# Breakout_SoC.net
KiCad netlist of a schematic drawn in Altium Designer
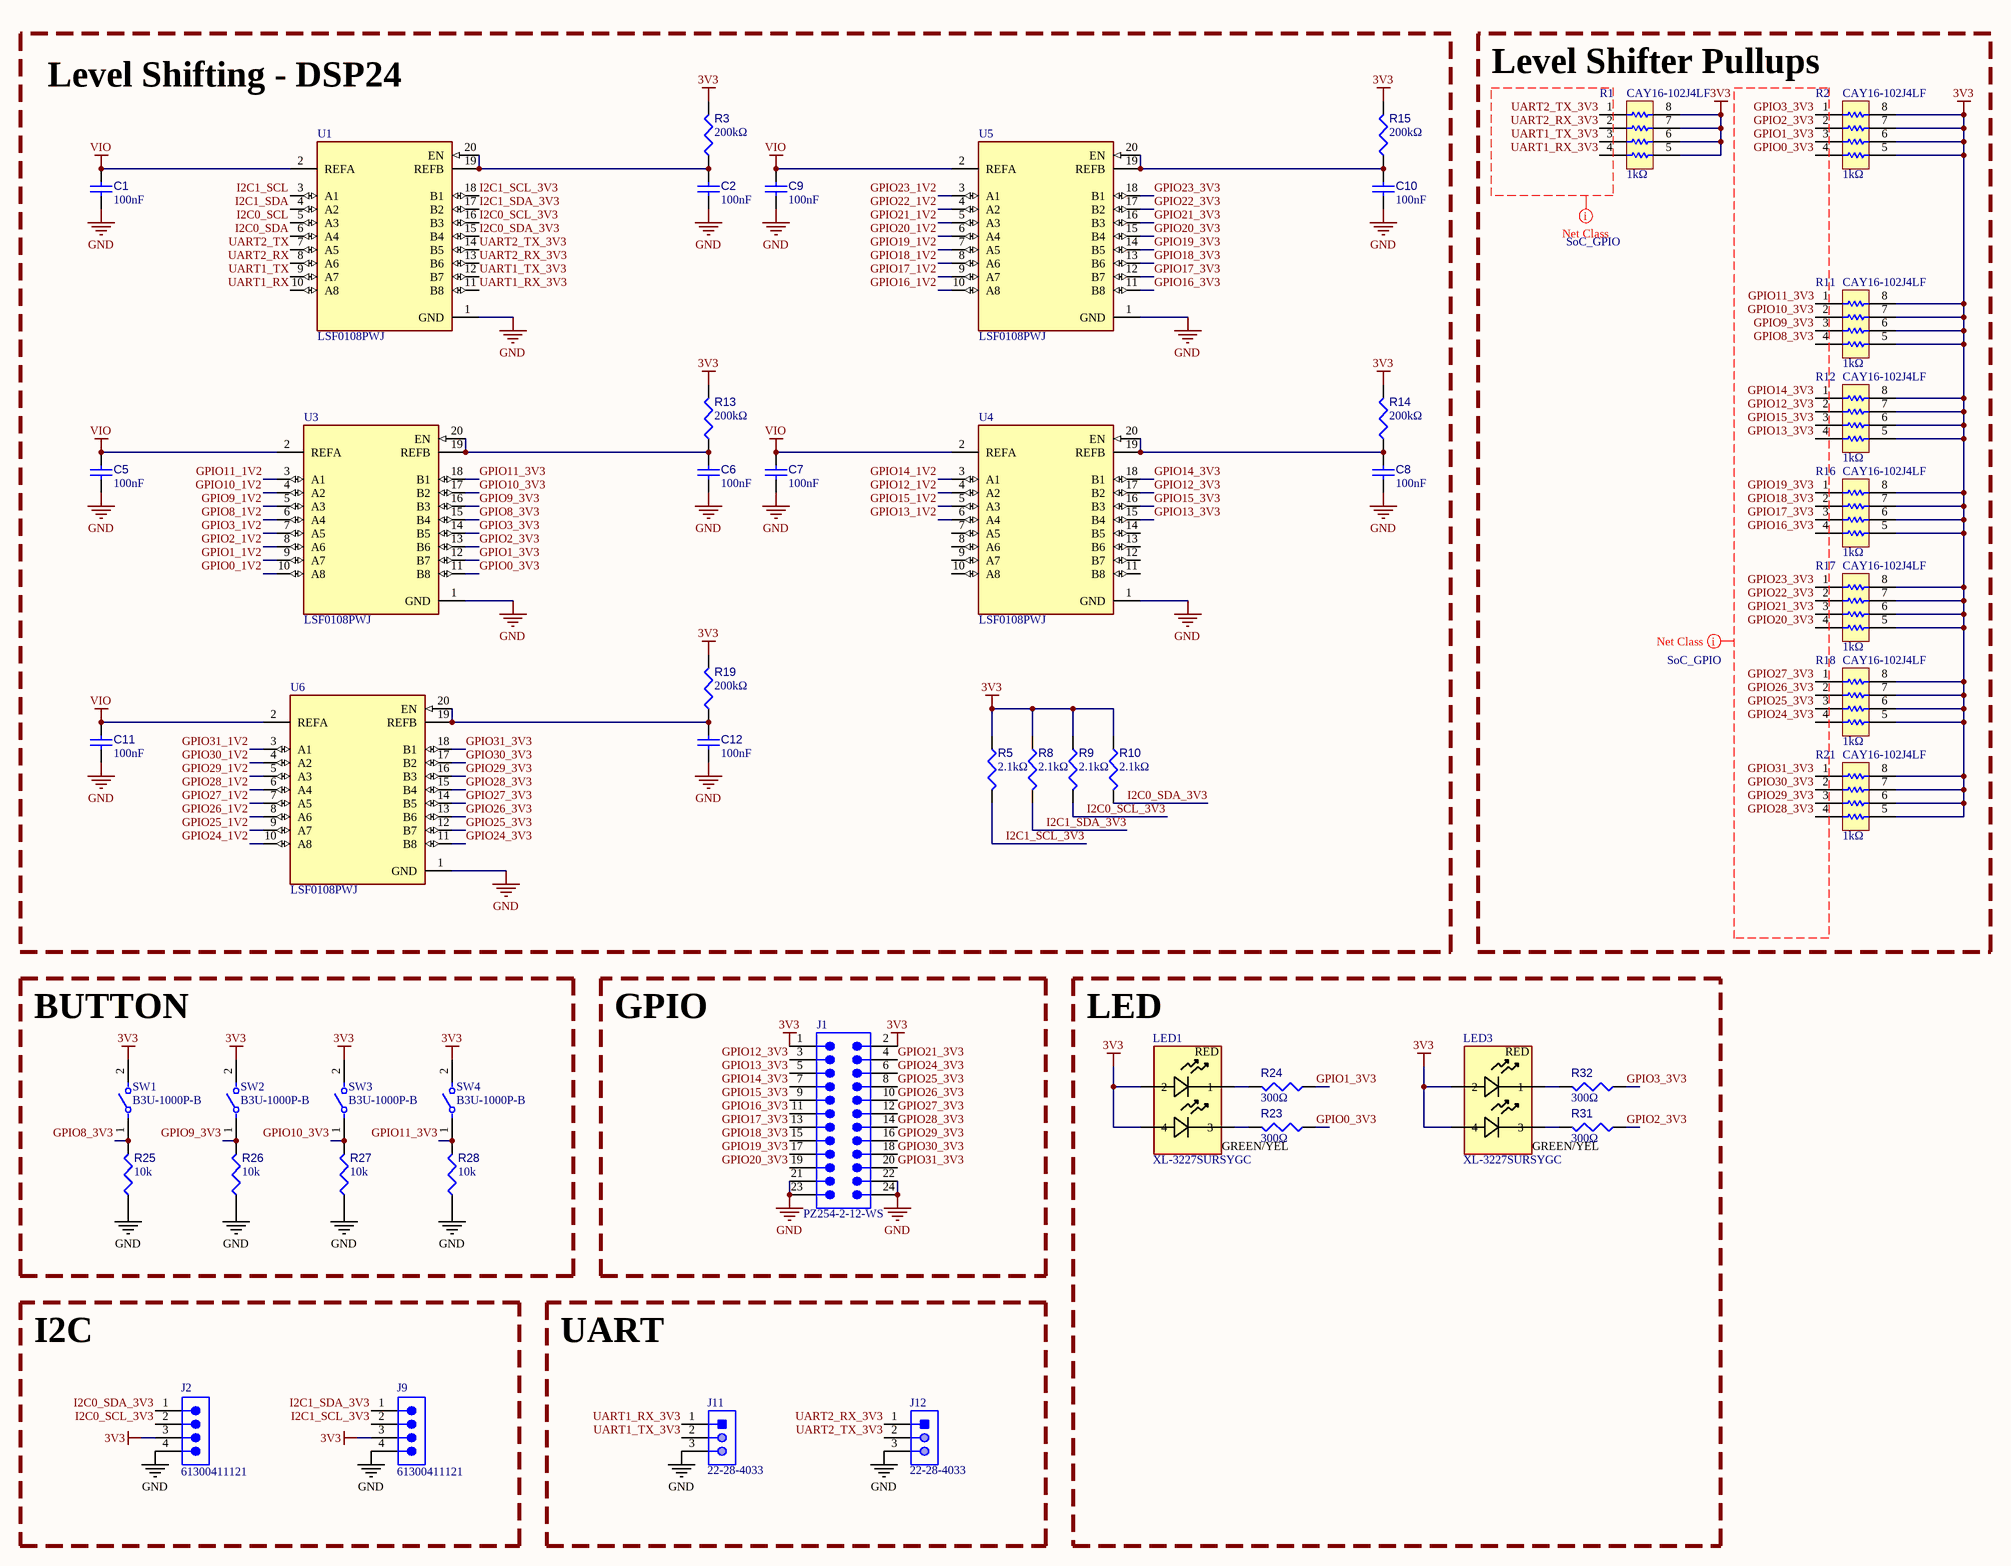
[diagram p0: Breakout_SoC.SchDoc]

(export (version "E")
  (design (tool "Eeschema 10.0.6"))
  (components
    (comp (ref "C1")
      (value "100nF")
      (footprint "CAP-0402-MFG")
      (description "0402-100n-10%-16V-X7R-AECQ200")
      (fields (field (name "TOLERANCE") "10%") (field (name "MANUFACTURER PART NUMBER") "CL05B104KO5VPNC"))
      (libsource (lib "UC Berkeley – EE194") (part "CAP-NP-2P"))
    )
    (comp (ref "C2")
      (value "100nF")
      (footprint "CAP-0402-MFG")
      (description "0402-100n-10%-16V-X7R-AECQ200")
      (fields (field (name "TOLERANCE") "10%") (field (name "MANUFACTURER PART NUMBER") "CL05B104KO5VPNC"))
      (libsource (lib "UC Berkeley – EE194") (part "CAP-NP-2P"))
    )
    (comp (ref "C5")
      (value "100nF")
      (footprint "CAP-0402-MFG")
      (description "0402-100n-10%-16V-X7R-AECQ200")
      (fields (field (name "TOLERANCE") "10%") (field (name "MANUFACTURER PART NUMBER") "CL05B104KO5VPNC"))
      (libsource (lib "UC Berkeley – EE194") (part "CAP-NP-2P"))
    )
    (comp (ref "C6")
      (value "100nF")
      (footprint "CAP-0402-MFG")
      (description "0402-100n-10%-16V-X7R-AECQ200")
      (fields (field (name "TOLERANCE") "10%") (field (name "MANUFACTURER PART NUMBER") "CL05B104KO5VPNC"))
      (libsource (lib "UC Berkeley – EE194") (part "CAP-NP-2P"))
    )
    (comp (ref "C7")
      (value "100nF")
      (footprint "CAP-0402-MFG")
      (description "0402-100n-10%-16V-X7R-AECQ200")
      (fields (field (name "TOLERANCE") "10%") (field (name "MANUFACTURER PART NUMBER") "CL05B104KO5VPNC"))
      (libsource (lib "UC Berkeley – EE194") (part "CAP-NP-2P"))
    )
    (comp (ref "C8")
      (value "100nF")
      (footprint "CAP-0402-MFG")
      (description "0402-100n-10%-16V-X7R-AECQ200")
      (fields (field (name "TOLERANCE") "10%") (field (name "MANUFACTURER PART NUMBER") "CL05B104KO5VPNC"))
      (libsource (lib "UC Berkeley – EE194") (part "CAP-NP-2P"))
    )
    (comp (ref "C9")
      (value "100nF")
      (footprint "CAP-0402-MFG")
      (description "0402-100n-10%-16V-X7R-AECQ200")
      (fields (field (name "TOLERANCE") "10%") (field (name "MANUFACTURER PART NUMBER") "CL05B104KO5VPNC"))
      (libsource (lib "UC Berkeley – EE194") (part "CAP-NP-2P"))
    )
    (comp (ref "C10")
      (value "100nF")
      (footprint "CAP-0402-MFG")
      (description "0402-100n-10%-16V-X7R-AECQ200")
      (fields (field (name "TOLERANCE") "10%") (field (name "MANUFACTURER PART NUMBER") "CL05B104KO5VPNC"))
      (libsource (lib "UC Berkeley – EE194") (part "CAP-NP-2P"))
    )
    (comp (ref "C11")
      (value "100nF")
      (footprint "CAP-0402-MFG")
      (description "0402-100n-10%-16V-X7R-AECQ200")
      (fields (field (name "TOLERANCE") "10%") (field (name "MANUFACTURER PART NUMBER") "CL05B104KO5VPNC"))
      (libsource (lib "UC Berkeley – EE194") (part "CAP-NP-2P"))
    )
    (comp (ref "C12")
      (value "100nF")
      (footprint "CAP-0402-MFG")
      (description "0402-100n-10%-16V-X7R-AECQ200")
      (fields (field (name "TOLERANCE") "10%") (field (name "MANUFACTURER PART NUMBER") "CL05B104KO5VPNC"))
      (libsource (lib "UC Berkeley – EE194") (part "CAP-NP-2P"))
    )
    (comp (ref "J1")
      (value "PZ254-2-12-WS")
      (footprint "610124249121")
      (description "Pin Header, 2.54MM Pitch, SMT Double Row Right Angled, 24 Pins")
      (libsource (lib "UC Berkeley – EE194") (part "Header_Male_2R_24P"))
    )
    (comp (ref "J2")
      (value "61300411121")
      (footprint "61300411121")
      (description "Conn Unshrouded Header HDR 4 POS 2.54mm Solder ST Thru-Hole Bag")
      (libsource (lib "UC Berkeley – EE194") (part "HEADER-MALE-4P-1R"))
    )
    (comp (ref "J9")
      (value "61300411121")
      (footprint "61300411121")
      (description "Conn Unshrouded Header HDR 4 POS 2.54mm Solder ST Thru-Hole Bag")
      (libsource (lib "UC Berkeley – EE194") (part "HEADER-MALE-4P-1R"))
    )
    (comp (ref "J11")
      (value "22-28-4033")
      (footprint "MOLX-22-28-4033_V")
      (libsource (lib "UC Berkeley – EE194") (part "HEADER-MALE-3P-1R"))
    )
    (comp (ref "J12")
      (value "22-28-4033")
      (footprint "MOLX-22-28-4033_V")
      (libsource (lib "UC Berkeley – EE194") (part "HEADER-MALE-3P-1R"))
    )
    (comp (ref "LED1")
      (value "XL-3227SURSYGC")
      (footprint "LED-1210-4P-MFG")
      (description "LED indicator light dual color red yellow green 1210 front facing")
      (libsource (lib "UC Berkeley – EE194") (part "LED-2COLOR-4P"))
    )
    (comp (ref "LED3")
      (value "XL-3227SURSYGC")
      (footprint "LED-1210-4P-MFG")
      (description "LED indicator light dual color red yellow green 1210 front facing")
      (libsource (lib "UC Berkeley – EE194") (part "LED-2COLOR-4P"))
    )
    (comp (ref "R1")
      (value "CAY16-102J4LF")
      (footprint "RES-4x0603-MFG")
      (description "Res Thick Film Array 1K Ohm 5% 0.25W(1/4W) ±200ppm/C ISOL 8-Pin 1206(4 X 0603) Convex SMD T/R")
      (fields (field (name "TOLERANCE") "5%") (field (name "ALTIUM_VALUE") "1kΩ"))
      (libsource (lib "UC Berkeley – EE194") (part "RES-x4-8P"))
    )
    (comp (ref "R2")
      (value "CAY16-102J4LF")
      (footprint "RES-4x0603-MFG")
      (description "Res Thick Film Array 1K Ohm 5% 0.25W(1/4W) ±200ppm/C ISOL 8-Pin 1206(4 X 0603) Convex SMD T/R")
      (fields (field (name "TOLERANCE") "5%") (field (name "ALTIUM_VALUE") "1kΩ"))
      (libsource (lib "UC Berkeley – EE194") (part "RES-x4-8P"))
    )
    (comp (ref "R3")
      (value "200kΩ")
      (footprint "RES-0402")
      (description "0402-200k-1%-1/16W-AEC-Q200")
      (fields (field (name "TOLERANCE") "1%") (field (name "POWER") "63mW"))
      (libsource (lib "UC Berkeley – EE194") (part "RES-2P"))
    )
    (comp (ref "R5")
      (value "2.1kΩ")
      (footprint "RES-0402")
      (description "0402-2.1k-1%-1/16W-AEC-Q200")
      (fields (field (name "POWER") "63mW") (field (name "MANUFACTURER PART NUMBER") "CRCW04022K10FKED"))
      (libsource (lib "UC Berkeley – EE194") (part "RES-2P"))
    )
    (comp (ref "R8")
      (value "2.1kΩ")
      (footprint "RES-0402")
      (description "0402-2.1k-1%-1/16W-AEC-Q200")
      (fields (field (name "POWER") "63mW") (field (name "MANUFACTURER PART NUMBER") "CRCW04022K10FKED"))
      (libsource (lib "UC Berkeley – EE194") (part "RES-2P"))
    )
    (comp (ref "R9")
      (value "2.1kΩ")
      (footprint "RES-0402")
      (description "0402-2.1k-1%-1/16W-AEC-Q200")
      (fields (field (name "POWER") "63mW") (field (name "MANUFACTURER PART NUMBER") "CRCW04022K10FKED"))
      (libsource (lib "UC Berkeley – EE194") (part "RES-2P"))
    )
    (comp (ref "R10")
      (value "2.1kΩ")
      (footprint "RES-0402")
      (description "0402-2.1k-1%-1/16W-AEC-Q200")
      (fields (field (name "POWER") "63mW") (field (name "MANUFACTURER PART NUMBER") "CRCW04022K10FKED"))
      (libsource (lib "UC Berkeley – EE194") (part "RES-2P"))
    )
    (comp (ref "R11")
      (value "CAY16-102J4LF")
      (footprint "RES-4x0603-MFG")
      (description "Res Thick Film Array 1K Ohm 5% 0.25W(1/4W) ±200ppm/C ISOL 8-Pin 1206(4 X 0603) Convex SMD T/R")
      (fields (field (name "TOLERANCE") "5%") (field (name "ALTIUM_VALUE") "1kΩ"))
      (libsource (lib "UC Berkeley – EE194") (part "RES-x4-8P"))
    )
    (comp (ref "R12")
      (value "CAY16-102J4LF")
      (footprint "RES-4x0603-MFG")
      (description "Res Thick Film Array 1K Ohm 5% 0.25W(1/4W) ±200ppm/C ISOL 8-Pin 1206(4 X 0603) Convex SMD T/R")
      (fields (field (name "TOLERANCE") "5%") (field (name "ALTIUM_VALUE") "1kΩ"))
      (libsource (lib "UC Berkeley – EE194") (part "RES-x4-8P"))
    )
    (comp (ref "R13")
      (value "200kΩ")
      (footprint "RES-0402")
      (description "0402-200k-1%-1/16W-AEC-Q200")
      (fields (field (name "TOLERANCE") "1%") (field (name "POWER") "63mW"))
      (libsource (lib "UC Berkeley – EE194") (part "RES-2P"))
    )
    (comp (ref "R14")
      (value "200kΩ")
      (footprint "RES-0402")
      (description "0402-200k-1%-1/16W-AEC-Q200")
      (fields (field (name "TOLERANCE") "1%") (field (name "POWER") "63mW"))
      (libsource (lib "UC Berkeley – EE194") (part "RES-2P"))
    )
    (comp (ref "R15")
      (value "200kΩ")
      (footprint "RES-0402")
      (description "0402-200k-1%-1/16W-AEC-Q200")
      (fields (field (name "TOLERANCE") "1%") (field (name "POWER") "63mW"))
      (libsource (lib "UC Berkeley – EE194") (part "RES-2P"))
    )
    (comp (ref "R16")
      (value "CAY16-102J4LF")
      (footprint "RES-4x0603-MFG")
      (description "Res Thick Film Array 1K Ohm 5% 0.25W(1/4W) ±200ppm/C ISOL 8-Pin 1206(4 X 0603) Convex SMD T/R")
      (fields (field (name "TOLERANCE") "5%") (field (name "ALTIUM_VALUE") "1kΩ"))
      (libsource (lib "UC Berkeley – EE194") (part "RES-x4-8P"))
    )
    (comp (ref "R17")
      (value "CAY16-102J4LF")
      (footprint "RES-4x0603-MFG")
      (description "Res Thick Film Array 1K Ohm 5% 0.25W(1/4W) ±200ppm/C ISOL 8-Pin 1206(4 X 0603) Convex SMD T/R")
      (fields (field (name "TOLERANCE") "5%") (field (name "ALTIUM_VALUE") "1kΩ"))
      (libsource (lib "UC Berkeley – EE194") (part "RES-x4-8P"))
    )
    (comp (ref "R18")
      (value "CAY16-102J4LF")
      (footprint "RES-4x0603-MFG")
      (description "Res Thick Film Array 1K Ohm 5% 0.25W(1/4W) ±200ppm/C ISOL 8-Pin 1206(4 X 0603) Convex SMD T/R")
      (fields (field (name "TOLERANCE") "5%") (field (name "ALTIUM_VALUE") "1kΩ"))
      (libsource (lib "UC Berkeley – EE194") (part "RES-x4-8P"))
    )
    (comp (ref "R19")
      (value "200kΩ")
      (footprint "RES-0402")
      (description "0402-200k-1%-1/16W-AEC-Q200")
      (fields (field (name "TOLERANCE") "1%") (field (name "POWER") "63mW"))
      (libsource (lib "UC Berkeley – EE194") (part "RES-2P"))
    )
    (comp (ref "R21")
      (value "CAY16-102J4LF")
      (footprint "RES-4x0603-MFG")
      (description "Res Thick Film Array 1K Ohm 5% 0.25W(1/4W) ±200ppm/C ISOL 8-Pin 1206(4 X 0603) Convex SMD T/R")
      (fields (field (name "TOLERANCE") "5%") (field (name "ALTIUM_VALUE") "1kΩ"))
      (libsource (lib "UC Berkeley – EE194") (part "RES-x4-8P"))
    )
    (comp (ref "R23")
      (value "300Ω")
      (footprint "RES-0402")
      (description "0402-300-1%-1/16W-AEC-Q200")
      (fields (field (name "MANUFACTURER PART NUMBER") "AC0402FR-07300RL") (field (name "POWER") "63mW"))
      (libsource (lib "UC Berkeley – EE194") (part "RES-2P"))
    )
    (comp (ref "R24")
      (value "300Ω")
      (footprint "RES-0402")
      (description "0402-300-1%-1/16W-AEC-Q200")
      (fields (field (name "MANUFACTURER PART NUMBER") "AC0402FR-07300RL") (field (name "POWER") "63mW"))
      (libsource (lib "UC Berkeley – EE194") (part "RES-2P"))
    )
    (comp (ref "R25")
      (value "10k")
      (footprint "RES-0402")
      (description "0402-10k-1%-1/16W-AEC-Q200")
      (fields (field (name "TOLERANCE") "1%") (field (name "MANUFACTURER PART NUMBER") "AC0402FR-0710KL"))
      (libsource (lib "UC Berkeley – EE194") (part "RES-2P"))
    )
    (comp (ref "R26")
      (value "10k")
      (footprint "RES-0402")
      (description "0402-10k-1%-1/16W-AEC-Q200")
      (fields (field (name "TOLERANCE") "1%") (field (name "MANUFACTURER PART NUMBER") "AC0402FR-0710KL"))
      (libsource (lib "UC Berkeley – EE194") (part "RES-2P"))
    )
    (comp (ref "R27")
      (value "10k")
      (footprint "RES-0402")
      (description "0402-10k-1%-1/16W-AEC-Q200")
      (fields (field (name "TOLERANCE") "1%") (field (name "MANUFACTURER PART NUMBER") "AC0402FR-0710KL"))
      (libsource (lib "UC Berkeley – EE194") (part "RES-2P"))
    )
    (comp (ref "R28")
      (value "10k")
      (footprint "RES-0402")
      (description "0402-10k-1%-1/16W-AEC-Q200")
      (fields (field (name "TOLERANCE") "1%") (field (name "MANUFACTURER PART NUMBER") "AC0402FR-0710KL"))
      (libsource (lib "UC Berkeley – EE194") (part "RES-2P"))
    )
    (comp (ref "R31")
      (value "300Ω")
      (footprint "RES-0402")
      (description "0402-300-1%-1/16W-AEC-Q200")
      (fields (field (name "MANUFACTURER PART NUMBER") "AC0402FR-07300RL") (field (name "POWER") "63mW"))
      (libsource (lib "UC Berkeley – EE194") (part "RES-2P"))
    )
    (comp (ref "R32")
      (value "300Ω")
      (footprint "RES-0402")
      (description "0402-300-1%-1/16W-AEC-Q200")
      (fields (field (name "MANUFACTURER PART NUMBER") "AC0402FR-07300RL") (field (name "POWER") "63mW"))
      (libsource (lib "UC Berkeley – EE194") (part "RES-2P"))
    )
    (comp (ref "SW1")
      (value "B3U-1000P-B")
      (footprint "FP-B3U-1000P-B-MFG")
      (description "Switch Tactile N.O. SPST Round Button Gull Wing 0.05A 12VDC 1.5N SMD Embossed T/R")
      (libsource (lib "UC Berkeley – EE194") (part "SWITCH-SPST-OFF-MOM-2P"))
    )
    (comp (ref "SW2")
      (value "B3U-1000P-B")
      (footprint "FP-B3U-1000P-B-MFG")
      (description "Switch Tactile N.O. SPST Round Button Gull Wing 0.05A 12VDC 1.5N SMD Embossed T/R")
      (libsource (lib "UC Berkeley – EE194") (part "SWITCH-SPST-OFF-MOM-2P"))
    )
    (comp (ref "SW3")
      (value "B3U-1000P-B")
      (footprint "FP-B3U-1000P-B-MFG")
      (description "Switch Tactile N.O. SPST Round Button Gull Wing 0.05A 12VDC 1.5N SMD Embossed T/R")
      (libsource (lib "UC Berkeley – EE194") (part "SWITCH-SPST-OFF-MOM-2P"))
    )
    (comp (ref "SW4")
      (value "B3U-1000P-B")
      (footprint "FP-B3U-1000P-B-MFG")
      (description "Switch Tactile N.O. SPST Round Button Gull Wing 0.05A 12VDC 1.5N SMD Embossed T/R")
      (libsource (lib "UC Berkeley – EE194") (part "SWITCH-SPST-OFF-MOM-2P"))
    )
    (comp (ref "U1")
      (value "LSF0108PWJ")
      (footprint "FP-TSSOP20-MFG")
      (description "LSF0108 - 8-bit bidirectional multi-voltage level translator; open-drain; push-pull")
      (libsource (lib "UC Berkeley – EE194") (part "LSF0108PWJ"))
    )
    (comp (ref "U3")
      (value "LSF0108PWJ")
      (footprint "FP-TSSOP20-MFG")
      (description "LSF0108 - 8-bit bidirectional multi-voltage level translator; open-drain; push-pull")
      (libsource (lib "UC Berkeley – EE194") (part "LSF0108PWJ"))
    )
    (comp (ref "U4")
      (value "LSF0108PWJ")
      (footprint "FP-TSSOP20-MFG")
      (description "LSF0108 - 8-bit bidirectional multi-voltage level translator; open-drain; push-pull")
      (libsource (lib "UC Berkeley – EE194") (part "LSF0108PWJ"))
    )
    (comp (ref "U5")
      (value "LSF0108PWJ")
      (footprint "FP-TSSOP20-MFG")
      (description "LSF0108 - 8-bit bidirectional multi-voltage level translator; open-drain; push-pull")
      (libsource (lib "UC Berkeley – EE194") (part "LSF0108PWJ"))
    )
    (comp (ref "U6")
      (value "LSF0108PWJ")
      (footprint "FP-TSSOP20-MFG")
      (description "LSF0108 - 8-bit bidirectional multi-voltage level translator; open-drain; push-pull")
      (libsource (lib "UC Berkeley – EE194") (part "LSF0108PWJ"))
    )
  )
  (nets
    (net (code "1") (name "/GPIO0_1V2") (class "Default")
      (node (ref "U3") (pin "10") (pinfunction "A8_10") (pintype "bidirectional"))
    )
    (net (code "2") (name "/GPIO0_3V3") (class "Default")
      (node (ref "R2") (pin "4") (pinfunction "4_4") (pintype "passive"))
      (node (ref "R23") (pin "2") (pinfunction "2_2") (pintype "passive"))
      (node (ref "U3") (pin "11") (pinfunction "B8_11") (pintype "bidirectional"))
    )
    (net (code "3") (name "/GPIO1_1V2") (class "Default")
      (node (ref "U3") (pin "9") (pinfunction "A7_9") (pintype "bidirectional"))
    )
    (net (code "4") (name "/GPIO1_3V3") (class "Default")
      (node (ref "R2") (pin "3") (pinfunction "3_3") (pintype "passive"))
      (node (ref "R24") (pin "2") (pinfunction "2_2") (pintype "passive"))
      (node (ref "U3") (pin "12") (pinfunction "B7_12") (pintype "bidirectional"))
    )
    (net (code "5") (name "/GPIO2_1V2") (class "Default")
      (node (ref "U3") (pin "8") (pinfunction "A6_8") (pintype "bidirectional"))
    )
    (net (code "6") (name "/GPIO2_3V3") (class "Default")
      (node (ref "R2") (pin "2") (pinfunction "2_2") (pintype "passive"))
      (node (ref "R31") (pin "2") (pinfunction "2_2") (pintype "passive"))
      (node (ref "U3") (pin "13") (pinfunction "B6_13") (pintype "bidirectional"))
    )
    (net (code "7") (name "/GPIO3_1V2") (class "Default")
      (node (ref "U3") (pin "7") (pinfunction "A5_7") (pintype "bidirectional"))
    )
    (net (code "8") (name "/GPIO3_3V3") (class "Default")
      (node (ref "R2") (pin "1") (pinfunction "1_1") (pintype "passive"))
      (node (ref "R32") (pin "2") (pinfunction "2_2") (pintype "passive"))
      (node (ref "U3") (pin "14") (pinfunction "B5_14") (pintype "bidirectional"))
    )
    (net (code "9") (name "/GPIO8_1V2") (class "Default")
      (node (ref "U3") (pin "6") (pinfunction "A4_6") (pintype "bidirectional"))
    )
    (net (code "10") (name "/GPIO8_3V3") (class "Default")
      (node (ref "R11") (pin "4") (pinfunction "4_4") (pintype "passive"))
      (node (ref "R25") (pin "2") (pinfunction "2_2") (pintype "passive"))
      (node (ref "SW1") (pin "1") (pinfunction "1_1") (pintype "passive"))
      (node (ref "U3") (pin "15") (pinfunction "B4_15") (pintype "bidirectional"))
    )
    (net (code "11") (name "/GPIO9_1V2") (class "Default")
      (node (ref "U3") (pin "5") (pinfunction "A3_5") (pintype "bidirectional"))
    )
    (net (code "12") (name "/GPIO9_3V3") (class "Default")
      (node (ref "R11") (pin "3") (pinfunction "3_3") (pintype "passive"))
      (node (ref "R26") (pin "2") (pinfunction "2_2") (pintype "passive"))
      (node (ref "SW2") (pin "1") (pinfunction "1_1") (pintype "passive"))
      (node (ref "U3") (pin "16") (pinfunction "B3_16") (pintype "bidirectional"))
    )
    (net (code "13") (name "/GPIO10_1V2") (class "Default")
      (node (ref "U3") (pin "4") (pinfunction "A2_4") (pintype "bidirectional"))
    )
    (net (code "14") (name "/GPIO10_3V3") (class "Default")
      (node (ref "R11") (pin "2") (pinfunction "2_2") (pintype "passive"))
      (node (ref "R27") (pin "2") (pinfunction "2_2") (pintype "passive"))
      (node (ref "SW3") (pin "1") (pinfunction "1_1") (pintype "passive"))
      (node (ref "U3") (pin "17") (pinfunction "B2_17") (pintype "bidirectional"))
    )
    (net (code "15") (name "/GPIO11_1V2") (class "Default")
      (node (ref "U3") (pin "3") (pinfunction "A1_3") (pintype "bidirectional"))
    )
    (net (code "16") (name "/GPIO11_3V3") (class "Default")
      (node (ref "R11") (pin "1") (pinfunction "1_1") (pintype "passive"))
      (node (ref "R28") (pin "2") (pinfunction "2_2") (pintype "passive"))
      (node (ref "SW4") (pin "1") (pinfunction "1_1") (pintype "passive"))
      (node (ref "U3") (pin "18") (pinfunction "B1_18") (pintype "bidirectional"))
    )
    (net (code "17") (name "/GPIO12_1V2") (class "Default")
      (node (ref "U4") (pin "4") (pinfunction "A2_4") (pintype "bidirectional"))
    )
    (net (code "18") (name "/GPIO12_3V3") (class "Default")
      (node (ref "J1") (pin "3") (pinfunction "3_3") (pintype "passive"))
      (node (ref "R12") (pin "2") (pinfunction "2_2") (pintype "passive"))
      (node (ref "U4") (pin "17") (pinfunction "B2_17") (pintype "bidirectional"))
    )
    (net (code "19") (name "/GPIO13_1V2") (class "Default")
      (node (ref "U4") (pin "6") (pinfunction "A4_6") (pintype "bidirectional"))
    )
    (net (code "20") (name "/GPIO13_3V3") (class "Default")
      (node (ref "J1") (pin "5") (pinfunction "5_5") (pintype "passive"))
      (node (ref "R12") (pin "4") (pinfunction "4_4") (pintype "passive"))
      (node (ref "U4") (pin "15") (pinfunction "B4_15") (pintype "bidirectional"))
    )
    (net (code "21") (name "/GPIO14_1V2") (class "Default")
      (node (ref "U4") (pin "3") (pinfunction "A1_3") (pintype "bidirectional"))
    )
    (net (code "22") (name "/GPIO14_3V3") (class "Default")
      (node (ref "J1") (pin "7") (pinfunction "7_7") (pintype "passive"))
      (node (ref "R12") (pin "1") (pinfunction "1_1") (pintype "passive"))
      (node (ref "U4") (pin "18") (pinfunction "B1_18") (pintype "bidirectional"))
    )
    (net (code "23") (name "/GPIO15_1V2") (class "Default")
      (node (ref "U4") (pin "5") (pinfunction "A3_5") (pintype "bidirectional"))
    )
    (net (code "24") (name "/GPIO15_3V3") (class "Default")
      (node (ref "J1") (pin "9") (pinfunction "9_9") (pintype "passive"))
      (node (ref "R12") (pin "3") (pinfunction "3_3") (pintype "passive"))
      (node (ref "U4") (pin "16") (pinfunction "B3_16") (pintype "bidirectional"))
    )
    (net (code "25") (name "/GPIO16_1V2") (class "Default")
      (node (ref "U5") (pin "10") (pinfunction "A8_10") (pintype "bidirectional"))
    )
    (net (code "26") (name "/GPIO16_3V3") (class "Default")
      (node (ref "J1") (pin "11") (pinfunction "11_11") (pintype "passive"))
      (node (ref "R16") (pin "4") (pinfunction "4_4") (pintype "passive"))
      (node (ref "U5") (pin "11") (pinfunction "B8_11") (pintype "bidirectional"))
    )
    (net (code "27") (name "/GPIO17_1V2") (class "Default")
      (node (ref "U5") (pin "9") (pinfunction "A7_9") (pintype "bidirectional"))
    )
    (net (code "28") (name "/GPIO17_3V3") (class "Default")
      (node (ref "J1") (pin "13") (pinfunction "13_13") (pintype "passive"))
      (node (ref "R16") (pin "3") (pinfunction "3_3") (pintype "passive"))
      (node (ref "U5") (pin "12") (pinfunction "B7_12") (pintype "bidirectional"))
    )
    (net (code "29") (name "/GPIO18_1V2") (class "Default")
      (node (ref "U5") (pin "8") (pinfunction "A6_8") (pintype "bidirectional"))
    )
    (net (code "30") (name "/GPIO18_3V3") (class "Default")
      (node (ref "J1") (pin "15") (pinfunction "15_15") (pintype "passive"))
      (node (ref "R16") (pin "2") (pinfunction "2_2") (pintype "passive"))
      (node (ref "U5") (pin "13") (pinfunction "B6_13") (pintype "bidirectional"))
    )
    (net (code "31") (name "/GPIO19_1V2") (class "Default")
      (node (ref "U5") (pin "7") (pinfunction "A5_7") (pintype "bidirectional"))
    )
    (net (code "32") (name "/GPIO19_3V3") (class "Default")
      (node (ref "J1") (pin "17") (pinfunction "17_17") (pintype "passive"))
      (node (ref "R16") (pin "1") (pinfunction "1_1") (pintype "passive"))
      (node (ref "U5") (pin "14") (pinfunction "B5_14") (pintype "bidirectional"))
    )
    (net (code "33") (name "/GPIO20_1V2") (class "Default")
      (node (ref "U5") (pin "6") (pinfunction "A4_6") (pintype "bidirectional"))
    )
    (net (code "34") (name "/GPIO20_3V3") (class "Default")
      (node (ref "J1") (pin "19") (pinfunction "19_19") (pintype "passive"))
      (node (ref "R17") (pin "4") (pinfunction "4_4") (pintype "passive"))
      (node (ref "U5") (pin "15") (pinfunction "B4_15") (pintype "bidirectional"))
    )
    (net (code "35") (name "/GPIO21_1V2") (class "Default")
      (node (ref "U5") (pin "5") (pinfunction "A3_5") (pintype "bidirectional"))
    )
    (net (code "36") (name "/GPIO21_3V3") (class "Default")
      (node (ref "J1") (pin "4") (pinfunction "4_4") (pintype "passive"))
      (node (ref "R17") (pin "3") (pinfunction "3_3") (pintype "passive"))
      (node (ref "U5") (pin "16") (pinfunction "B3_16") (pintype "bidirectional"))
    )
    (net (code "37") (name "/GPIO22_1V2") (class "Default")
      (node (ref "U5") (pin "4") (pinfunction "A2_4") (pintype "bidirectional"))
    )
    (net (code "38") (name "/GPIO22_3V3") (class "Default")
      (node (ref "R17") (pin "2") (pinfunction "2_2") (pintype "passive"))
      (node (ref "U5") (pin "17") (pinfunction "B2_17") (pintype "bidirectional"))
    )
    (net (code "39") (name "/GPIO23_1V2") (class "Default")
      (node (ref "U5") (pin "3") (pinfunction "A1_3") (pintype "bidirectional"))
    )
    (net (code "40") (name "/GPIO23_3V3") (class "Default")
      (node (ref "R17") (pin "1") (pinfunction "1_1") (pintype "passive"))
      (node (ref "U5") (pin "18") (pinfunction "B1_18") (pintype "bidirectional"))
    )
    (net (code "41") (name "/GPIO24_1V2") (class "Default")
      (node (ref "U6") (pin "10") (pinfunction "A8_10") (pintype "bidirectional"))
    )
    (net (code "42") (name "/GPIO24_3V3") (class "Default")
      (node (ref "J1") (pin "6") (pinfunction "6_6") (pintype "passive"))
      (node (ref "R18") (pin "4") (pinfunction "4_4") (pintype "passive"))
      (node (ref "U6") (pin "11") (pinfunction "B8_11") (pintype "bidirectional"))
    )
    (net (code "43") (name "/GPIO25_1V2") (class "Default")
      (node (ref "U6") (pin "9") (pinfunction "A7_9") (pintype "bidirectional"))
    )
    (net (code "44") (name "/GPIO25_3V3") (class "Default")
      (node (ref "J1") (pin "8") (pinfunction "8_8") (pintype "passive"))
      (node (ref "R18") (pin "3") (pinfunction "3_3") (pintype "passive"))
      (node (ref "U6") (pin "12") (pinfunction "B7_12") (pintype "bidirectional"))
    )
    (net (code "45") (name "/GPIO26_1V2") (class "Default")
      (node (ref "U6") (pin "8") (pinfunction "A6_8") (pintype "bidirectional"))
    )
    (net (code "46") (name "/GPIO26_3V3") (class "Default")
      (node (ref "J1") (pin "10") (pinfunction "10_10") (pintype "passive"))
      (node (ref "R18") (pin "2") (pinfunction "2_2") (pintype "passive"))
      (node (ref "U6") (pin "13") (pinfunction "B6_13") (pintype "bidirectional"))
    )
    (net (code "47") (name "/GPIO27_1V2") (class "Default")
      (node (ref "U6") (pin "7") (pinfunction "A5_7") (pintype "bidirectional"))
    )
    (net (code "48") (name "/GPIO27_3V3") (class "Default")
      (node (ref "J1") (pin "12") (pinfunction "12_12") (pintype "passive"))
      (node (ref "R18") (pin "1") (pinfunction "1_1") (pintype "passive"))
      (node (ref "U6") (pin "14") (pinfunction "B5_14") (pintype "bidirectional"))
    )
    (net (code "49") (name "/GPIO28_1V2") (class "Default")
      (node (ref "U6") (pin "6") (pinfunction "A4_6") (pintype "bidirectional"))
    )
    (net (code "50") (name "/GPIO28_3V3") (class "Default")
      (node (ref "J1") (pin "14") (pinfunction "14_14") (pintype "passive"))
      (node (ref "R21") (pin "4") (pinfunction "4_4") (pintype "passive"))
      (node (ref "U6") (pin "15") (pinfunction "B4_15") (pintype "bidirectional"))
    )
    (net (code "51") (name "/GPIO29_1V2") (class "Default")
      (node (ref "U6") (pin "5") (pinfunction "A3_5") (pintype "bidirectional"))
    )
    (net (code "52") (name "/GPIO29_3V3") (class "Default")
      (node (ref "J1") (pin "16") (pinfunction "16_16") (pintype "passive"))
      (node (ref "R21") (pin "3") (pinfunction "3_3") (pintype "passive"))
      (node (ref "U6") (pin "16") (pinfunction "B3_16") (pintype "bidirectional"))
    )
    (net (code "53") (name "/GPIO30_1V2") (class "Default")
      (node (ref "U6") (pin "4") (pinfunction "A2_4") (pintype "bidirectional"))
    )
    (net (code "54") (name "/GPIO30_3V3") (class "Default")
      (node (ref "J1") (pin "18") (pinfunction "18_18") (pintype "passive"))
      (node (ref "R21") (pin "2") (pinfunction "2_2") (pintype "passive"))
      (node (ref "U6") (pin "17") (pinfunction "B2_17") (pintype "bidirectional"))
    )
    (net (code "55") (name "/GPIO31_1V2") (class "Default")
      (node (ref "U6") (pin "3") (pinfunction "A1_3") (pintype "bidirectional"))
    )
    (net (code "56") (name "/GPIO31_3V3") (class "Default")
      (node (ref "J1") (pin "20") (pinfunction "20_20") (pintype "passive"))
      (node (ref "R21") (pin "1") (pinfunction "1_1") (pintype "passive"))
      (node (ref "U6") (pin "18") (pinfunction "B1_18") (pintype "bidirectional"))
    )
    (net (code "57") (name "/I2C0_SCL") (class "Default")
      (node (ref "U1") (pin "5") (pinfunction "A3_5") (pintype "bidirectional"))
    )
    (net (code "58") (name "/I2C0_SCL_3V3") (class "Default")
      (node (ref "J2") (pin "2") (pinfunction "2_2") (pintype "passive"))
      (node (ref "R9") (pin "2") (pinfunction "2_2") (pintype "passive"))
      (node (ref "U1") (pin "16") (pinfunction "B3_16") (pintype "bidirectional"))
    )
    (net (code "59") (name "/I2C0_SDA") (class "Default")
      (node (ref "U1") (pin "6") (pinfunction "A4_6") (pintype "bidirectional"))
    )
    (net (code "60") (name "/I2C0_SDA_3V3") (class "Default")
      (node (ref "J2") (pin "1") (pinfunction "1_1") (pintype "passive"))
      (node (ref "R10") (pin "2") (pinfunction "2_2") (pintype "passive"))
      (node (ref "U1") (pin "15") (pinfunction "B4_15") (pintype "bidirectional"))
    )
    (net (code "61") (name "/I2C1_SCL") (class "Default")
      (node (ref "U1") (pin "3") (pinfunction "A1_3") (pintype "bidirectional"))
    )
    (net (code "62") (name "/I2C1_SCL_3V3") (class "Default")
      (node (ref "J9") (pin "2") (pinfunction "2_2") (pintype "passive"))
      (node (ref "R5") (pin "2") (pinfunction "2_2") (pintype "passive"))
      (node (ref "U1") (pin "18") (pinfunction "B1_18") (pintype "bidirectional"))
    )
    (net (code "63") (name "/I2C1_SDA") (class "Default")
      (node (ref "U1") (pin "4") (pinfunction "A2_4") (pintype "bidirectional"))
    )
    (net (code "64") (name "/I2C1_SDA_3V3") (class "Default")
      (node (ref "J9") (pin "1") (pinfunction "1_1") (pintype "passive"))
      (node (ref "R8") (pin "2") (pinfunction "2_2") (pintype "passive"))
      (node (ref "U1") (pin "17") (pinfunction "B2_17") (pintype "bidirectional"))
    )
    (net (code "65") (name "/UART1_RX") (class "Default")
      (node (ref "U1") (pin "10") (pinfunction "A8_10") (pintype "bidirectional"))
    )
    (net (code "66") (name "/UART1_RX_3V3") (class "Default")
      (node (ref "J11") (pin "1") (pinfunction "1_1") (pintype "passive"))
      (node (ref "R1") (pin "4") (pinfunction "4_4") (pintype "passive"))
      (node (ref "U1") (pin "11") (pinfunction "B8_11") (pintype "bidirectional"))
    )
    (net (code "67") (name "/UART1_TX") (class "Default")
      (node (ref "U1") (pin "9") (pinfunction "A7_9") (pintype "bidirectional"))
    )
    (net (code "68") (name "/UART1_TX_3V3") (class "Default")
      (node (ref "J11") (pin "2") (pinfunction "2_2") (pintype "passive"))
      (node (ref "R1") (pin "3") (pinfunction "3_3") (pintype "passive"))
      (node (ref "U1") (pin "12") (pinfunction "B7_12") (pintype "bidirectional"))
    )
    (net (code "69") (name "/UART2_RX") (class "Default")
      (node (ref "U1") (pin "8") (pinfunction "A6_8") (pintype "bidirectional"))
    )
    (net (code "70") (name "/UART2_RX_3V3") (class "Default")
      (node (ref "J12") (pin "1") (pinfunction "1_1") (pintype "passive"))
      (node (ref "R1") (pin "2") (pinfunction "2_2") (pintype "passive"))
      (node (ref "U1") (pin "13") (pinfunction "B6_13") (pintype "bidirectional"))
    )
    (net (code "71") (name "/UART2_TX") (class "Default")
      (node (ref "U1") (pin "7") (pinfunction "A5_7") (pintype "bidirectional"))
    )
    (net (code "72") (name "/UART2_TX_3V3") (class "Default")
      (node (ref "J12") (pin "2") (pinfunction "2_2") (pintype "passive"))
      (node (ref "R1") (pin "1") (pinfunction "1_1") (pintype "passive"))
      (node (ref "U1") (pin "14") (pinfunction "B5_14") (pintype "bidirectional"))
    )
    (net (code "73") (name "3V3") (class "Default")
      (node (ref "J1") (pin "1") (pinfunction "1_1") (pintype "passive"))
      (node (ref "J1") (pin "2") (pinfunction "2_2") (pintype "passive"))
      (node (ref "J2") (pin "3") (pinfunction "3_3") (pintype "passive"))
      (node (ref "J9") (pin "3") (pinfunction "3_3") (pintype "passive"))
      (node (ref "LED1") (pin "2") (pinfunction "2_2") (pintype "passive"))
      (node (ref "LED1") (pin "4") (pinfunction "4_4") (pintype "passive"))
      (node (ref "LED3") (pin "2") (pinfunction "2_2") (pintype "passive"))
      (node (ref "LED3") (pin "4") (pinfunction "4_4") (pintype "passive"))
      (node (ref "R1") (pin "5") (pinfunction "5_5") (pintype "passive"))
      (node (ref "R1") (pin "6") (pinfunction "6_6") (pintype "passive"))
      (node (ref "R1") (pin "7") (pinfunction "7_7") (pintype "passive"))
      (node (ref "R1") (pin "8") (pinfunction "8_8") (pintype "passive"))
      (node (ref "R10") (pin "1") (pinfunction "1_1") (pintype "passive"))
      (node (ref "R11") (pin "5") (pinfunction "5_5") (pintype "passive"))
      (node (ref "R11") (pin "6") (pinfunction "6_6") (pintype "passive"))
      (node (ref "R11") (pin "7") (pinfunction "7_7") (pintype "passive"))
      (node (ref "R11") (pin "8") (pinfunction "8_8") (pintype "passive"))
      (node (ref "R12") (pin "5") (pinfunction "5_5") (pintype "passive"))
      (node (ref "R12") (pin "6") (pinfunction "6_6") (pintype "passive"))
      (node (ref "R12") (pin "7") (pinfunction "7_7") (pintype "passive"))
      (node (ref "R12") (pin "8") (pinfunction "8_8") (pintype "passive"))
      (node (ref "R13") (pin "2") (pinfunction "2_2") (pintype "passive"))
      (node (ref "R14") (pin "2") (pinfunction "2_2") (pintype "passive"))
      (node (ref "R15") (pin "2") (pinfunction "2_2") (pintype "passive"))
      (node (ref "R16") (pin "5") (pinfunction "5_5") (pintype "passive"))
      (node (ref "R16") (pin "6") (pinfunction "6_6") (pintype "passive"))
      (node (ref "R16") (pin "7") (pinfunction "7_7") (pintype "passive"))
      (node (ref "R16") (pin "8") (pinfunction "8_8") (pintype "passive"))
      (node (ref "R17") (pin "5") (pinfunction "5_5") (pintype "passive"))
      (node (ref "R17") (pin "6") (pinfunction "6_6") (pintype "passive"))
      (node (ref "R17") (pin "7") (pinfunction "7_7") (pintype "passive"))
      (node (ref "R17") (pin "8") (pinfunction "8_8") (pintype "passive"))
      (node (ref "R18") (pin "5") (pinfunction "5_5") (pintype "passive"))
      (node (ref "R18") (pin "6") (pinfunction "6_6") (pintype "passive"))
      (node (ref "R18") (pin "7") (pinfunction "7_7") (pintype "passive"))
      (node (ref "R18") (pin "8") (pinfunction "8_8") (pintype "passive"))
      (node (ref "R19") (pin "2") (pinfunction "2_2") (pintype "passive"))
      (node (ref "R2") (pin "5") (pinfunction "5_5") (pintype "passive"))
      (node (ref "R2") (pin "6") (pinfunction "6_6") (pintype "passive"))
      (node (ref "R2") (pin "7") (pinfunction "7_7") (pintype "passive"))
      (node (ref "R2") (pin "8") (pinfunction "8_8") (pintype "passive"))
      (node (ref "R21") (pin "5") (pinfunction "5_5") (pintype "passive"))
      (node (ref "R21") (pin "6") (pinfunction "6_6") (pintype "passive"))
      (node (ref "R21") (pin "7") (pinfunction "7_7") (pintype "passive"))
      (node (ref "R21") (pin "8") (pinfunction "8_8") (pintype "passive"))
      (node (ref "R3") (pin "2") (pinfunction "2_2") (pintype "passive"))
      (node (ref "R5") (pin "1") (pinfunction "1_1") (pintype "passive"))
      (node (ref "R8") (pin "1") (pinfunction "1_1") (pintype "passive"))
      (node (ref "R9") (pin "1") (pinfunction "1_1") (pintype "passive"))
      (node (ref "SW1") (pin "2") (pinfunction "2_2") (pintype "passive"))
      (node (ref "SW2") (pin "2") (pinfunction "2_2") (pintype "passive"))
      (node (ref "SW3") (pin "2") (pinfunction "2_2") (pintype "passive"))
      (node (ref "SW4") (pin "2") (pinfunction "2_2") (pintype "passive"))
    )
    (net (code "74") (name "GND") (class "Default")
      (node (ref "C1") (pin "1") (pinfunction "1_1") (pintype "passive"))
      (node (ref "C10") (pin "2") (pinfunction "2_2") (pintype "passive"))
      (node (ref "C11") (pin "2") (pinfunction "2_2") (pintype "passive"))
      (node (ref "C12") (pin "2") (pinfunction "2_2") (pintype "passive"))
      (node (ref "C2") (pin "2") (pinfunction "2_2") (pintype "passive"))
      (node (ref "C5") (pin "1") (pinfunction "1_1") (pintype "passive"))
      (node (ref "C6") (pin "2") (pinfunction "2_2") (pintype "passive"))
      (node (ref "C7") (pin "1") (pinfunction "1_1") (pintype "passive"))
      (node (ref "C8") (pin "2") (pinfunction "2_2") (pintype "passive"))
      (node (ref "C9") (pin "1") (pinfunction "1_1") (pintype "passive"))
      (node (ref "J1") (pin "21") (pinfunction "21_21") (pintype "passive"))
      (node (ref "J1") (pin "22") (pinfunction "22_22") (pintype "passive"))
      (node (ref "J1") (pin "23") (pinfunction "23_23") (pintype "passive"))
      (node (ref "J1") (pin "24") (pinfunction "24_24") (pintype "passive"))
      (node (ref "J11") (pin "3") (pinfunction "3_3") (pintype "passive"))
      (node (ref "J12") (pin "3") (pinfunction "3_3") (pintype "passive"))
      (node (ref "J2") (pin "4") (pinfunction "4_4") (pintype "passive"))
      (node (ref "J9") (pin "4") (pinfunction "4_4") (pintype "passive"))
      (node (ref "R25") (pin "1") (pinfunction "1_1") (pintype "passive"))
      (node (ref "R26") (pin "1") (pinfunction "1_1") (pintype "passive"))
      (node (ref "R27") (pin "1") (pinfunction "1_1") (pintype "passive"))
      (node (ref "R28") (pin "1") (pinfunction "1_1") (pintype "passive"))
      (node (ref "U1") (pin "1") (pinfunction "GND_1") (pintype "power_in"))
      (node (ref "U3") (pin "1") (pinfunction "GND_1") (pintype "power_in"))
      (node (ref "U4") (pin "1") (pinfunction "GND_1") (pintype "power_in"))
      (node (ref "U5") (pin "1") (pinfunction "GND_1") (pintype "power_in"))
      (node (ref "U6") (pin "1") (pinfunction "GND_1") (pintype "power_in"))
    )
    (net (code "75") (name "Net-(LED1-Pad1)") (class "Default")
      (node (ref "LED1") (pin "1") (pinfunction "1_1") (pintype "passive"))
      (node (ref "R24") (pin "1") (pinfunction "1_1") (pintype "passive"))
    )
    (net (code "76") (name "Net-(LED1-Pad3)") (class "Default")
      (node (ref "LED1") (pin "3") (pinfunction "3_3") (pintype "passive"))
      (node (ref "R23") (pin "1") (pinfunction "1_1") (pintype "passive"))
    )
    (net (code "77") (name "Net-(LED3-Pad1)") (class "Default")
      (node (ref "LED3") (pin "1") (pinfunction "1_1") (pintype "passive"))
      (node (ref "R32") (pin "1") (pinfunction "1_1") (pintype "passive"))
    )
    (net (code "78") (name "Net-(LED3-Pad3)") (class "Default")
      (node (ref "LED3") (pin "3") (pinfunction "3_3") (pintype "passive"))
      (node (ref "R31") (pin "1") (pinfunction "1_1") (pintype "passive"))
    )
    (net (code "79") (name "Net-(U1-EN)") (class "Default")
      (node (ref "C2") (pin "1") (pinfunction "1_1") (pintype "passive"))
      (node (ref "R3") (pin "1") (pinfunction "1_1") (pintype "passive"))
      (node (ref "U1") (pin "19") (pinfunction "REFB_19") (pintype "power_in"))
      (node (ref "U1") (pin "20") (pinfunction "EN_20") (pintype "input"))
    )
    (net (code "80") (name "Net-(U3-EN)") (class "Default")
      (node (ref "C6") (pin "1") (pinfunction "1_1") (pintype "passive"))
      (node (ref "R13") (pin "1") (pinfunction "1_1") (pintype "passive"))
      (node (ref "U3") (pin "19") (pinfunction "REFB_19") (pintype "power_in"))
      (node (ref "U3") (pin "20") (pinfunction "EN_20") (pintype "input"))
    )
    (net (code "81") (name "Net-(U4-EN)") (class "Default")
      (node (ref "C8") (pin "1") (pinfunction "1_1") (pintype "passive"))
      (node (ref "R14") (pin "1") (pinfunction "1_1") (pintype "passive"))
      (node (ref "U4") (pin "19") (pinfunction "REFB_19") (pintype "power_in"))
      (node (ref "U4") (pin "20") (pinfunction "EN_20") (pintype "input"))
    )
    (net (code "82") (name "Net-(U5-EN)") (class "Default")
      (node (ref "C10") (pin "1") (pinfunction "1_1") (pintype "passive"))
      (node (ref "R15") (pin "1") (pinfunction "1_1") (pintype "passive"))
      (node (ref "U5") (pin "19") (pinfunction "REFB_19") (pintype "power_in"))
      (node (ref "U5") (pin "20") (pinfunction "EN_20") (pintype "input"))
    )
    (net (code "83") (name "Net-(U6-EN)") (class "Default")
      (node (ref "C12") (pin "1") (pinfunction "1_1") (pintype "passive"))
      (node (ref "R19") (pin "1") (pinfunction "1_1") (pintype "passive"))
      (node (ref "U6") (pin "19") (pinfunction "REFB_19") (pintype "power_in"))
      (node (ref "U6") (pin "20") (pinfunction "EN_20") (pintype "input"))
    )
    (net (code "84") (name "VIO") (class "Default")
      (node (ref "C1") (pin "2") (pinfunction "2_2") (pintype "passive"))
      (node (ref "C11") (pin "1") (pinfunction "1_1") (pintype "passive"))
      (node (ref "C5") (pin "2") (pinfunction "2_2") (pintype "passive"))
      (node (ref "C7") (pin "2") (pinfunction "2_2") (pintype "passive"))
      (node (ref "C9") (pin "2") (pinfunction "2_2") (pintype "passive"))
      (node (ref "U1") (pin "2") (pinfunction "REFA_2") (pintype "power_in"))
      (node (ref "U3") (pin "2") (pinfunction "REFA_2") (pintype "power_in"))
      (node (ref "U4") (pin "2") (pinfunction "REFA_2") (pintype "power_in"))
      (node (ref "U5") (pin "2") (pinfunction "REFA_2") (pintype "power_in"))
      (node (ref "U6") (pin "2") (pinfunction "REFA_2") (pintype "power_in"))
    )
    (net (code "85") (name "unconnected-(U4-A5-Pad7)") (class "Default")
      (node (ref "U4") (pin "7") (pinfunction "A5_7") (pintype "bidirectional"))
    )
    (net (code "86") (name "unconnected-(U4-A6-Pad8)") (class "Default")
      (node (ref "U4") (pin "8") (pinfunction "A6_8") (pintype "bidirectional"))
    )
    (net (code "87") (name "unconnected-(U4-A7-Pad9)") (class "Default")
      (node (ref "U4") (pin "9") (pinfunction "A7_9") (pintype "bidirectional"))
    )
    (net (code "88") (name "unconnected-(U4-A8-Pad10)") (class "Default")
      (node (ref "U4") (pin "10") (pinfunction "A8_10") (pintype "bidirectional"))
    )
    (net (code "89") (name "unconnected-(U4-B5-Pad14)") (class "Default")
      (node (ref "U4") (pin "14") (pinfunction "B5_14") (pintype "bidirectional"))
    )
    (net (code "90") (name "unconnected-(U4-B6-Pad13)") (class "Default")
      (node (ref "U4") (pin "13") (pinfunction "B6_13") (pintype "bidirectional"))
    )
    (net (code "91") (name "unconnected-(U4-B7-Pad12)") (class "Default")
      (node (ref "U4") (pin "12") (pinfunction "B7_12") (pintype "bidirectional"))
    )
    (net (code "92") (name "unconnected-(U4-B8-Pad11)") (class "Default")
      (node (ref "U4") (pin "11") (pinfunction "B8_11") (pintype "bidirectional"))
    )
  )
)
